# files.net
KiCad netlist of a schematic drawn in EasyEDA Pro
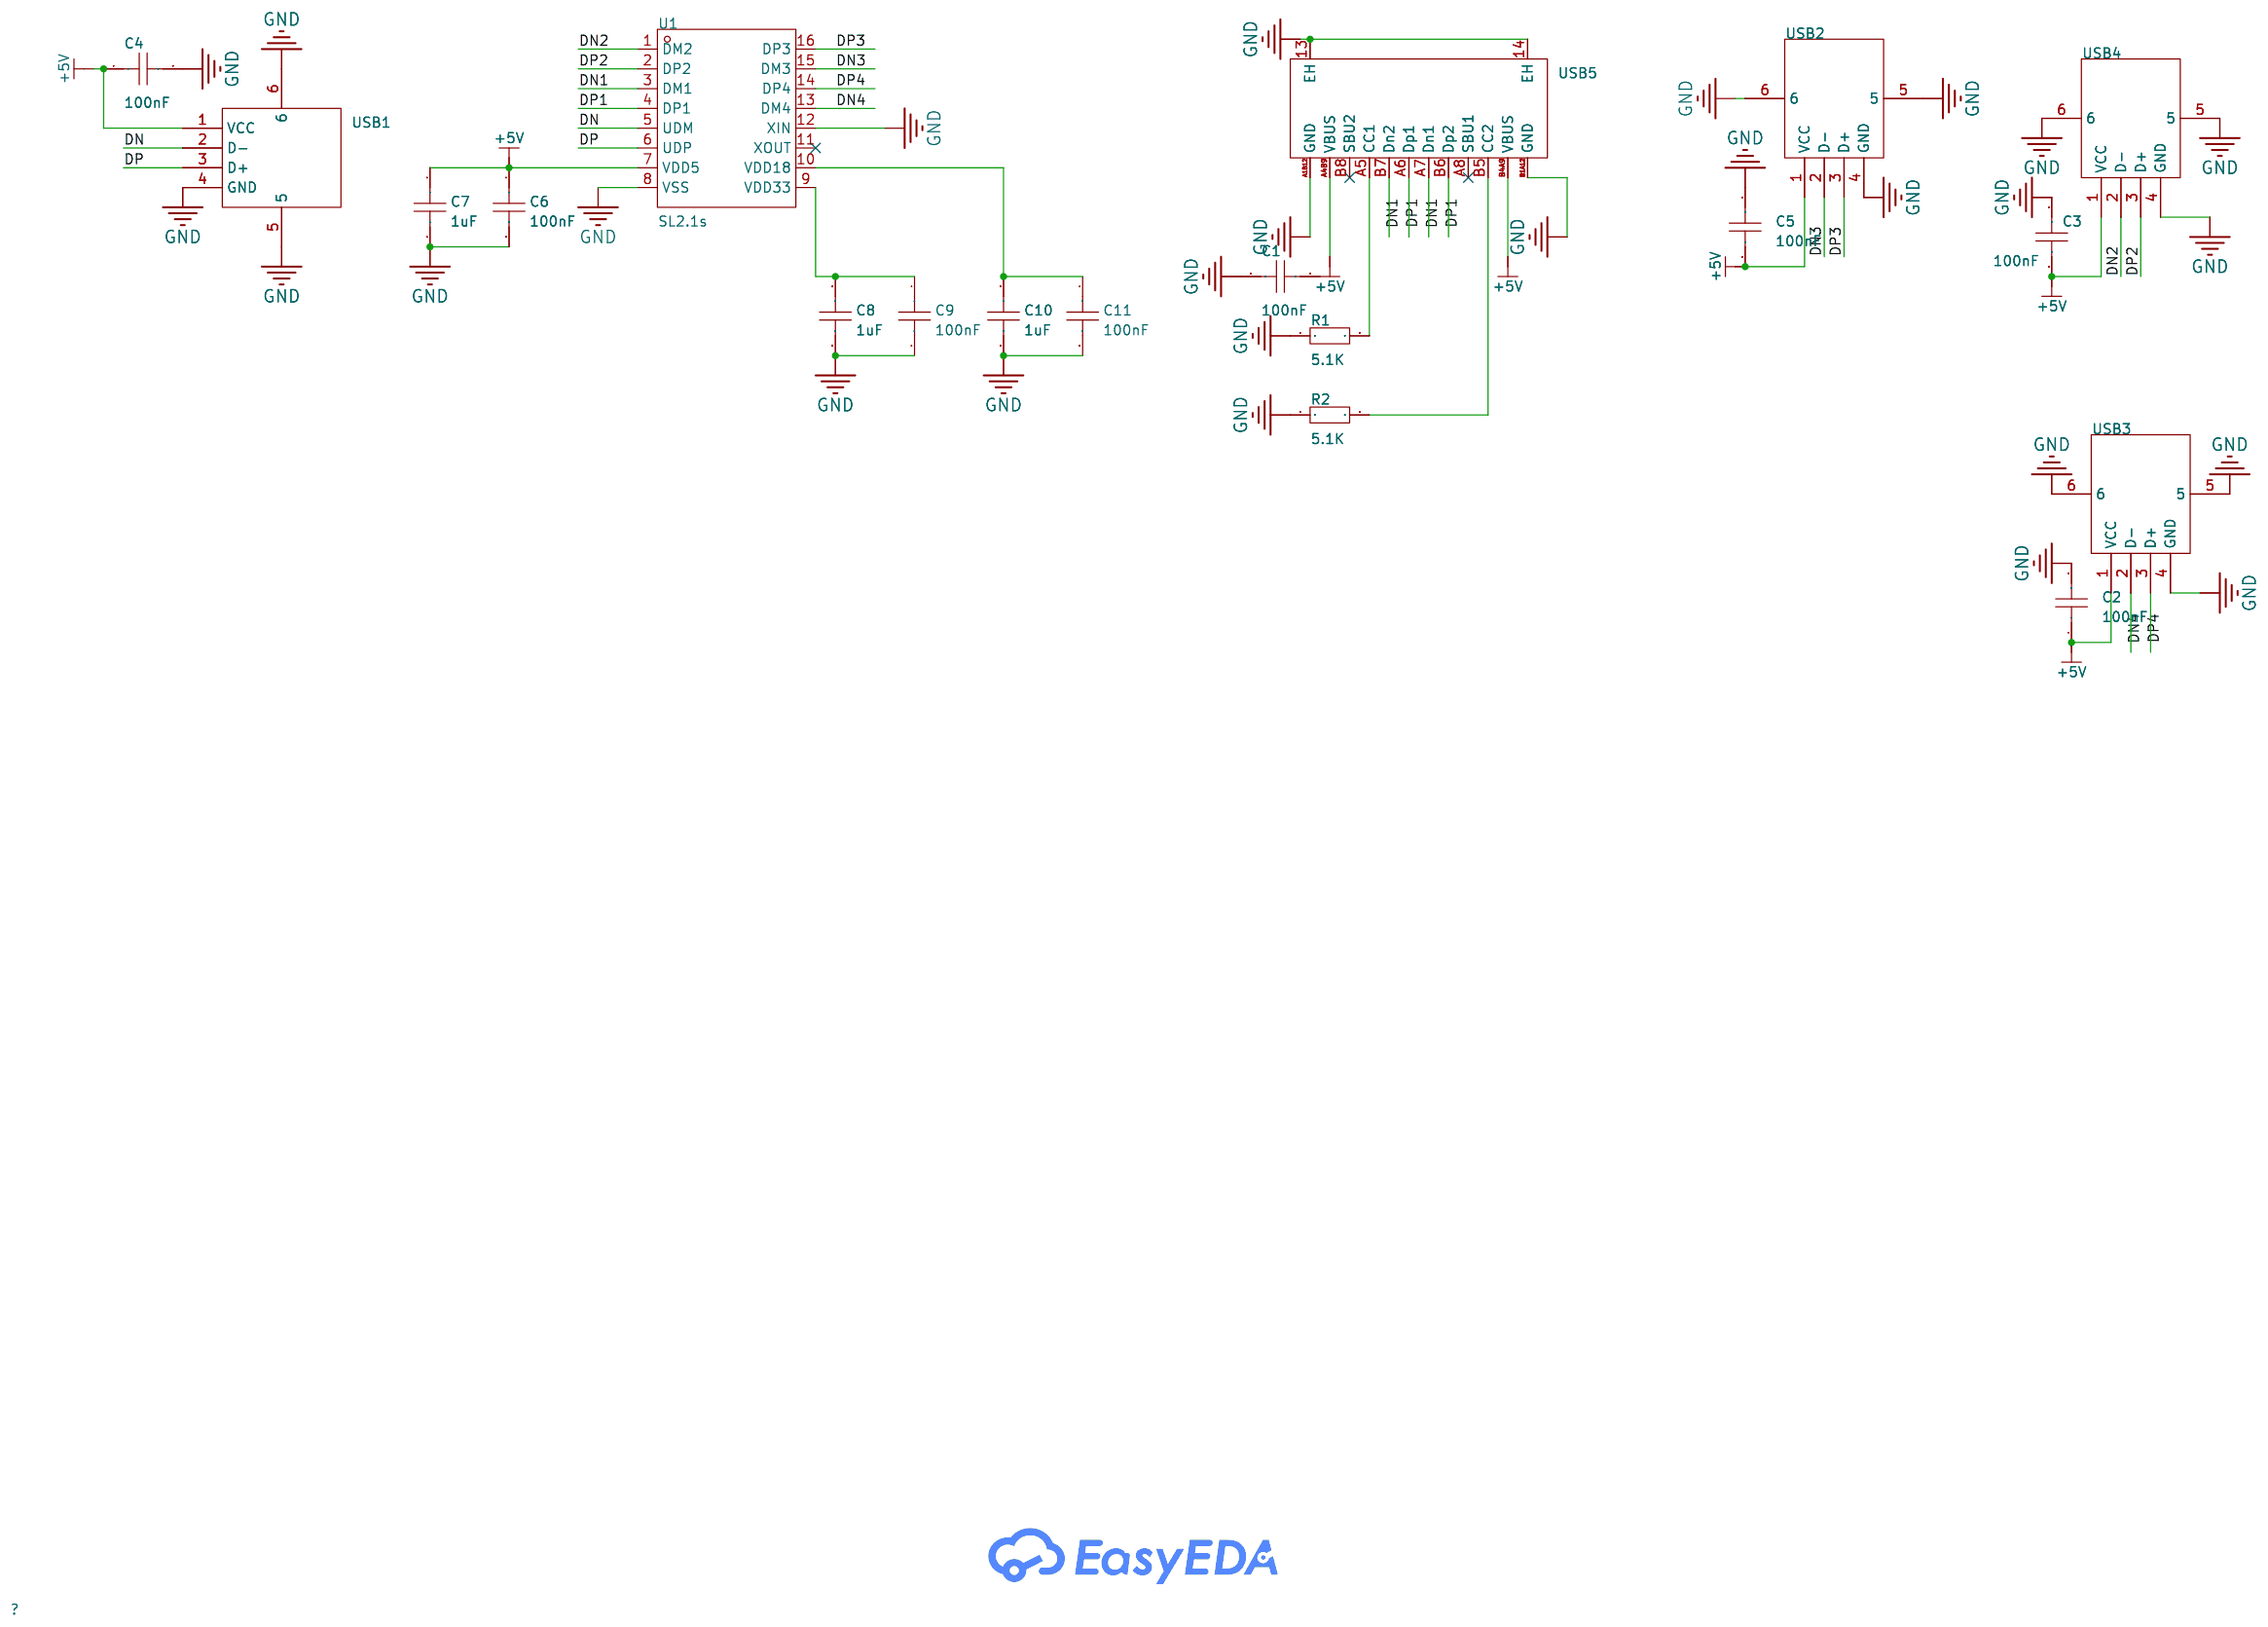
[diagram p0: schematic sheet]

(export (version "E")
  (design (tool "Eeschema 10.0.6"))
  (components
    (comp (ref "C1")
      (value "100nF")
      (footprint "easyedapro:C0603")
      (libsource (lib "easyedapro") (part "CAP"))
    )
    (comp (ref "C2")
      (value "100nF")
      (footprint "easyedapro:C0603")
      (libsource (lib "easyedapro") (part "CAP"))
    )
    (comp (ref "C3")
      (value "100nF")
      (footprint "easyedapro:C0603")
      (libsource (lib "easyedapro") (part "CAP"))
    )
    (comp (ref "C4")
      (value "100nF")
      (footprint "easyedapro:C0603")
      (libsource (lib "easyedapro") (part "CAP"))
    )
    (comp (ref "C5")
      (value "100nF")
      (footprint "easyedapro:C0603")
      (libsource (lib "easyedapro") (part "CAP"))
    )
    (comp (ref "C6")
      (value "100nF")
      (footprint "easyedapro:C0603")
      (libsource (lib "easyedapro") (part "CAP"))
    )
    (comp (ref "C7") (value "1uF") (footprint "easyedapro:C0603") (libsource (lib "easyedapro") (part "CAP")))
    (comp (ref "C8") (value "1uF") (footprint "easyedapro:C0603") (libsource (lib "easyedapro") (part "CAP")))
    (comp (ref "C9")
      (value "100nF")
      (footprint "easyedapro:C0603")
      (libsource (lib "easyedapro") (part "CAP"))
    )
    (comp (ref "C10")
      (value "1uF")
      (footprint "easyedapro:C0603")
      (libsource (lib "easyedapro") (part "CAP"))
    )
    (comp (ref "C11")
      (value "100nF")
      (footprint "easyedapro:C0603")
      (libsource (lib "easyedapro") (part "CAP"))
    )
    (comp (ref "R1")
      (value "5.1K")
      (footprint "easyedapro:R0603")
      (libsource (lib "easyedapro") (part "Res"))
    )
    (comp (ref "R2")
      (value "5.1K")
      (footprint "easyedapro:R0603")
      (libsource (lib "easyedapro") (part "Res"))
    )
    (comp (ref "U1")
      (value "SL2.1s")
      (footprint "easyedapro:SSOP-16_L4.6-W2.6-P0.53-LS4.0-BL")
      (fields (field (name "Manufacturer") "CoreChips(和芯润德)"))
      (libsource (lib "easyedapro") (part "SL2.1S"))
    )
    (comp (ref "USB1")
      (value "10.0 QHHTZB6.3")
      (footprint "easyedapro:USB-A-TH_10.0QHHTZB6.3")
      (fields (field (name "Manufacturer") "SHOU HAN(首韩)"))
      (libsource (lib "easyedapro") (part "10.0 QHHTZB6.3"))
    )
    (comp (ref "USB2")
      (value "10.0 QHHTZB6.3")
      (footprint "easyedapro:USB-A-TH_10.0QHHTZB6.3")
      (fields (field (name "Manufacturer") "SHOU HAN(首韩)"))
      (libsource (lib "easyedapro") (part "10.0 QHHTZB6.3"))
    )
    (comp (ref "USB3")
      (value "10.0 QHHTZB6.3")
      (footprint "easyedapro:USB-A-TH_10.0QHHTZB6.3")
      (fields (field (name "Manufacturer") "SHOU HAN(首韩)"))
      (libsource (lib "easyedapro") (part "10.0 QHHTZB6.3"))
    )
    (comp (ref "USB4")
      (value "10.0 QHHTZB6.3")
      (footprint "easyedapro:USB-A-TH_10.0QHHTZB6.3")
      (fields (field (name "Manufacturer") "SHOU HAN(首韩)"))
      (libsource (lib "easyedapro") (part "10.0 QHHTZB6.3"))
    )
    (comp (ref "USB5")
      (value "TYPE-C 16PIN 2MD(073)")
      (footprint "easyedapro:USB-C-SMD_TYPE-C-16PIN-2MD-073")
      (fields (field (name "Manufacturer") "SHOU HAN(首韩)"))
      (libsource (lib "easyedapro") (part "TYPE-C 16PIN 2MD(073)"))
    )
  )
  (nets
    (net (code "1") (name "+5V") (class "Default")
      (node (ref "C2") (pin "1") (pinfunction "1_1") (pintype "input"))
      (node (ref "C3") (pin "2") (pinfunction "2_2") (pintype "input"))
      (node (ref "C4") (pin "1") (pinfunction "1_1") (pintype "input"))
      (node (ref "C5") (pin "2") (pinfunction "2_2") (pintype "input"))
      (node (ref "C6") (pin "1") (pinfunction "1_1") (pintype "input"))
      (node (ref "C7") (pin "1") (pinfunction "1_1") (pintype "input"))
      (node (ref "U1") (pin "7") (pinfunction "VDD5_7") (pintype "unspecified"))
      (node (ref "USB1") (pin "1") (pinfunction "VCC_1") (pintype "unspecified"))
      (node (ref "USB2") (pin "1") (pinfunction "VCC_1") (pintype "unspecified"))
      (node (ref "USB3") (pin "1") (pinfunction "VCC_1") (pintype "unspecified"))
      (node (ref "USB4") (pin "1") (pinfunction "VCC_1") (pintype "unspecified"))
      (node (ref "USB5") (pin "A4B9") (pinfunction "VBUS_A4B9") (pintype "unspecified"))
      (node (ref "USB5") (pin "B4A9") (pinfunction "VBUS_B4A9") (pintype "unspecified"))
    )
    (net (code "2") (name "/DN") (class "Default")
      (node (ref "U1") (pin "5") (pinfunction "UDM_5") (pintype "unspecified"))
      (node (ref "USB1") (pin "2") (pinfunction "D-_2") (pintype "unspecified"))
    )
    (net (code "3") (name "/DN1") (class "Default")
      (node (ref "U1") (pin "3") (pinfunction "DM1_3") (pintype "unspecified"))
      (node (ref "USB5") (pin "A7") (pinfunction "Dn1_A7") (pintype "unspecified"))
      (node (ref "USB5") (pin "B7") (pinfunction "Dn2_B7") (pintype "unspecified"))
    )
    (net (code "4") (name "/DN2") (class "Default")
      (node (ref "U1") (pin "1") (pinfunction "DM2_1") (pintype "unspecified"))
      (node (ref "USB4") (pin "2") (pinfunction "D-_2") (pintype "unspecified"))
    )
    (net (code "5") (name "/DN3") (class "Default")
      (node (ref "U1") (pin "15") (pinfunction "DM3_15") (pintype "unspecified"))
      (node (ref "USB2") (pin "2") (pinfunction "D-_2") (pintype "unspecified"))
    )
    (net (code "6") (name "/DN4") (class "Default")
      (node (ref "U1") (pin "13") (pinfunction "DM4_13") (pintype "unspecified"))
      (node (ref "USB3") (pin "2") (pinfunction "D-_2") (pintype "unspecified"))
    )
    (net (code "7") (name "/DP") (class "Default")
      (node (ref "U1") (pin "6") (pinfunction "UDP_6") (pintype "unspecified"))
      (node (ref "USB1") (pin "3") (pinfunction "D+_3") (pintype "unspecified"))
    )
    (net (code "8") (name "/DP1") (class "Default")
      (node (ref "U1") (pin "4") (pinfunction "DP1_4") (pintype "unspecified"))
      (node (ref "USB5") (pin "A6") (pinfunction "Dp1_A6") (pintype "unspecified"))
      (node (ref "USB5") (pin "B6") (pinfunction "Dp2_B6") (pintype "unspecified"))
    )
    (net (code "9") (name "/DP2") (class "Default")
      (node (ref "U1") (pin "2") (pinfunction "DP2_2") (pintype "unspecified"))
      (node (ref "USB4") (pin "3") (pinfunction "D+_3") (pintype "unspecified"))
    )
    (net (code "10") (name "/DP3") (class "Default")
      (node (ref "U1") (pin "16") (pinfunction "DP3_16") (pintype "unspecified"))
      (node (ref "USB2") (pin "3") (pinfunction "D+_3") (pintype "unspecified"))
    )
    (net (code "11") (name "/DP4") (class "Default")
      (node (ref "U1") (pin "14") (pinfunction "DP4_14") (pintype "unspecified"))
      (node (ref "USB3") (pin "3") (pinfunction "D+_3") (pintype "unspecified"))
    )
    (net (code "12") (name "GND") (class "Default")
      (node (ref "C1") (pin "2") (pinfunction "2_2") (pintype "input"))
      (node (ref "C10") (pin "2") (pinfunction "2_2") (pintype "input"))
      (node (ref "C11") (pin "2") (pinfunction "2_2") (pintype "input"))
      (node (ref "C2") (pin "2") (pinfunction "2_2") (pintype "input"))
      (node (ref "C3") (pin "1") (pinfunction "1_1") (pintype "input"))
      (node (ref "C4") (pin "2") (pinfunction "2_2") (pintype "input"))
      (node (ref "C5") (pin "1") (pinfunction "1_1") (pintype "input"))
      (node (ref "C6") (pin "2") (pinfunction "2_2") (pintype "input"))
      (node (ref "C7") (pin "2") (pinfunction "2_2") (pintype "input"))
      (node (ref "C8") (pin "2") (pinfunction "2_2") (pintype "input"))
      (node (ref "C9") (pin "2") (pinfunction "2_2") (pintype "input"))
      (node (ref "R1") (pin "1") (pinfunction "1_1") (pintype "input"))
      (node (ref "R2") (pin "1") (pinfunction "1_1") (pintype "input"))
      (node (ref "U1") (pin "12") (pinfunction "XIN_12") (pintype "unspecified"))
      (node (ref "U1") (pin "8") (pinfunction "VSS_8") (pintype "unspecified"))
      (node (ref "USB1") (pin "4") (pinfunction "GND_4") (pintype "unspecified"))
      (node (ref "USB1") (pin "5") (pinfunction "5_5") (pintype "unspecified"))
      (node (ref "USB1") (pin "6") (pinfunction "6_6") (pintype "unspecified"))
      (node (ref "USB2") (pin "4") (pinfunction "GND_4") (pintype "unspecified"))
      (node (ref "USB2") (pin "5") (pinfunction "5_5") (pintype "unspecified"))
      (node (ref "USB2") (pin "6") (pinfunction "6_6") (pintype "unspecified"))
      (node (ref "USB3") (pin "4") (pinfunction "GND_4") (pintype "unspecified"))
      (node (ref "USB3") (pin "5") (pinfunction "5_5") (pintype "unspecified"))
      (node (ref "USB3") (pin "6") (pinfunction "6_6") (pintype "unspecified"))
      (node (ref "USB4") (pin "4") (pinfunction "GND_4") (pintype "unspecified"))
      (node (ref "USB4") (pin "5") (pinfunction "5_5") (pintype "unspecified"))
      (node (ref "USB4") (pin "6") (pinfunction "6_6") (pintype "unspecified"))
      (node (ref "USB5") (pin "13") (pinfunction "EH_13") (pintype "unspecified"))
      (node (ref "USB5") (pin "14") (pinfunction "EH_14") (pintype "unspecified"))
      (node (ref "USB5") (pin "A1B12") (pinfunction "GND_A1B12") (pintype "unspecified"))
      (node (ref "USB5") (pin "B1A12") (pinfunction "GND_B1A12") (pintype "unspecified"))
    )
    (net (code "13") (name "Net-(U1-VDD18)") (class "Default")
      (node (ref "C10") (pin "1") (pinfunction "1_1") (pintype "input"))
      (node (ref "C11") (pin "1") (pinfunction "1_1") (pintype "input"))
      (node (ref "U1") (pin "10") (pinfunction "VDD18_10") (pintype "unspecified"))
    )
    (net (code "14") (name "Net-(U1-VDD33)") (class "Default")
      (node (ref "C8") (pin "1") (pinfunction "1_1") (pintype "input"))
      (node (ref "C9") (pin "1") (pinfunction "1_1") (pintype "input"))
      (node (ref "U1") (pin "9") (pinfunction "VDD33_9") (pintype "unspecified"))
    )
    (net (code "15") (name "Net-(USB5-CC1)") (class "Default")
      (node (ref "R1") (pin "2") (pinfunction "2_2") (pintype "input"))
      (node (ref "USB5") (pin "A5") (pinfunction "CC1_A5") (pintype "unspecified"))
    )
    (net (code "16") (name "Net-(USB5-CC2)") (class "Default")
      (node (ref "R2") (pin "2") (pinfunction "2_2") (pintype "input"))
      (node (ref "USB5") (pin "B5") (pinfunction "CC2_B5") (pintype "unspecified"))
    )
    (net (code "17") (name "unconnected-(C1-Pad1)") (class "Default")
      (node (ref "C1") (pin "1") (pinfunction "1_1") (pintype "input"))
    )
    (net (code "18") (name "unconnected-(U1-XOUT-Pad11)") (class "Default")
      (node (ref "U1") (pin "11") (pinfunction "XOUT_11") (pintype "unspecified+no_connect"))
    )
    (net (code "19") (name "unconnected-(USB5-SBU1-PadA8)") (class "Default")
      (node (ref "USB5") (pin "A8") (pinfunction "SBU1_A8") (pintype "unspecified+no_connect"))
    )
    (net (code "20") (name "unconnected-(USB5-SBU2-PadB8)") (class "Default")
      (node (ref "USB5") (pin "B8") (pinfunction "SBU2_B8") (pintype "unspecified+no_connect"))
    )
  )
)
